# cdf-single-driver.net
KiCad netlist of a schematic drawn in EAGLE
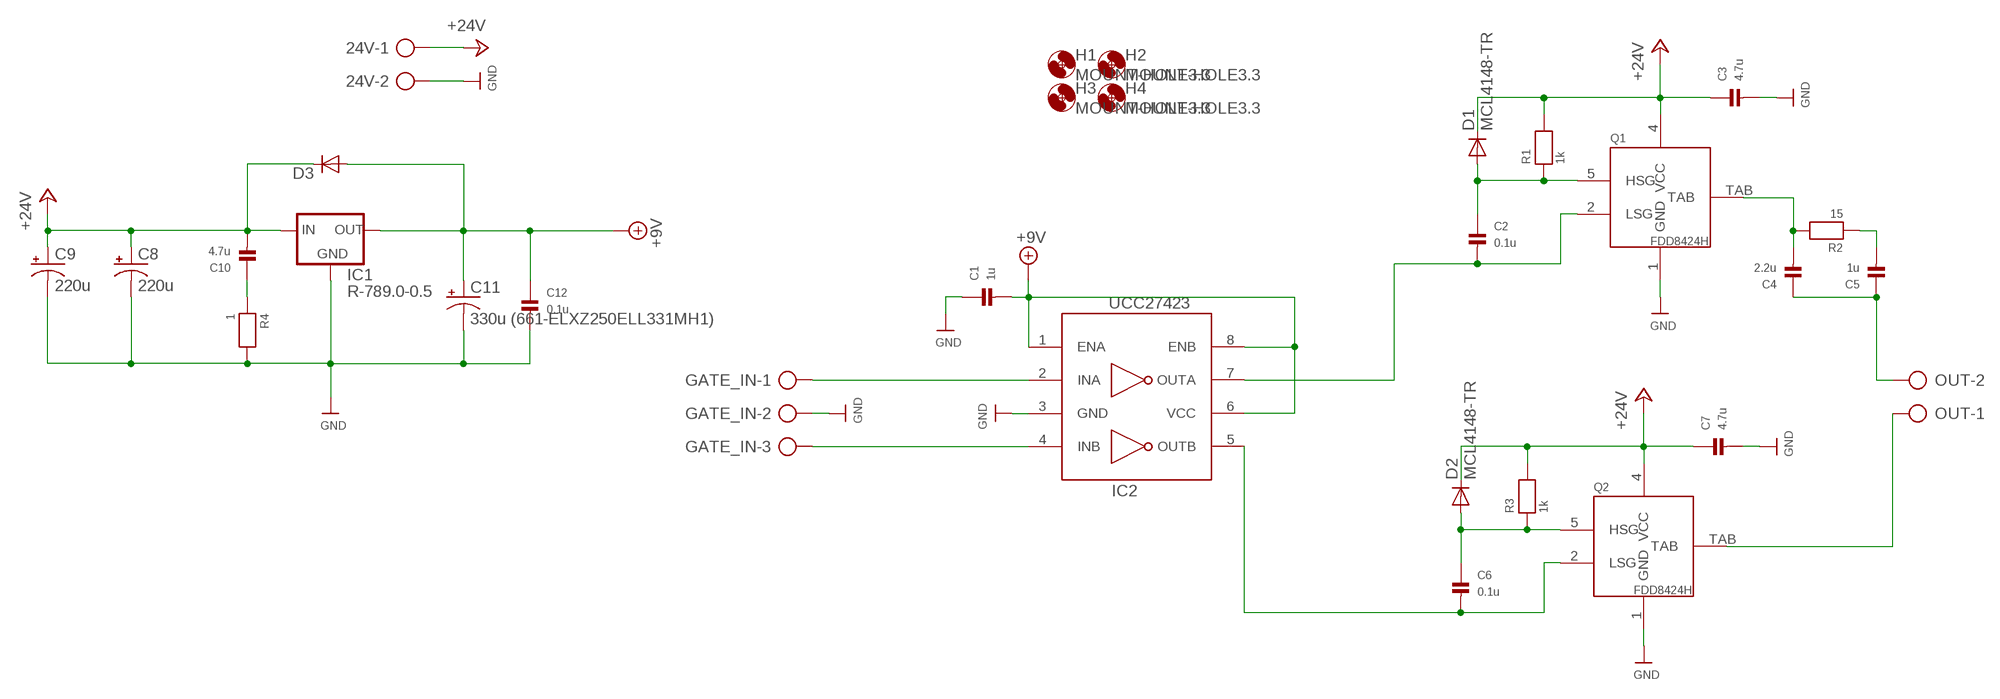
[diagram p0: schematic, sheet 1]

(export (version "E")
  (design (tool "Eeschema 10.0.6"))
  (components
    (comp (ref "24V")
      (value "AK500/2")
      (footprint "eagle-import:AK500_2")
      (libsource (lib "eagle-import") (part "AK500/2"))
    )
    (comp (ref "C1")
      (value "1u")
      (footprint "eagle-import:0805")
      (libsource (lib "eagle-import") (part "CAP_CERAMIC0805"))
    )
    (comp (ref "C2")
      (value "0.1u")
      (footprint "eagle-import:0805")
      (libsource (lib "eagle-import") (part "CAP_CERAMIC0805"))
    )
    (comp (ref "C3")
      (value "4.7u")
      (footprint "eagle-import:0805")
      (libsource (lib "eagle-import") (part "CAP_CERAMIC0805"))
    )
    (comp (ref "C4")
      (value "2.2u")
      (footprint "eagle-import:0805")
      (libsource (lib "eagle-import") (part "CAP_CERAMIC0805"))
    )
    (comp (ref "C5")
      (value "1u")
      (footprint "eagle-import:0805")
      (libsource (lib "eagle-import") (part "CAP_CERAMIC0805"))
    )
    (comp (ref "C6")
      (value "0.1u")
      (footprint "eagle-import:0805")
      (libsource (lib "eagle-import") (part "CAP_CERAMIC0805"))
    )
    (comp (ref "C7")
      (value "4.7u")
      (footprint "eagle-import:0805")
      (libsource (lib "eagle-import") (part "CAP_CERAMIC0805"))
    )
    (comp (ref "C8")
      (value "220u")
      (footprint "eagle-import:E3,5-8")
      (libsource (lib "eagle-import") (part "CPOL-USE3.5-8"))
    )
    (comp (ref "C9")
      (value "220u")
      (footprint "eagle-import:E3,5-8")
      (libsource (lib "eagle-import") (part "CPOL-USE3.5-8"))
    )
    (comp (ref "C10")
      (value "4.7u")
      (footprint "eagle-import:0805")
      (libsource (lib "eagle-import") (part "CAP_CERAMIC0805"))
    )
    (comp (ref "C11")
      (value "330u (661-ELXZ250ELL331MH1)")
      (footprint "eagle-import:E3,5-8")
      (libsource (lib "eagle-import") (part "CPOL-USE3.5-8"))
    )
    (comp (ref "C12")
      (value "0.1u")
      (footprint "eagle-import:0805")
      (libsource (lib "eagle-import") (part "CAP_CERAMIC0805"))
    )
    (comp (ref "D1")
      (value "MCL4148-TR")
      (footprint "eagle-import:MICROMELF-W")
      (libsource (lib "eagle-import") (part "DIODE-MICROMELF-W"))
    )
    (comp (ref "D2")
      (value "MCL4148-TR")
      (footprint "eagle-import:MICROMELF-W")
      (libsource (lib "eagle-import") (part "DIODE-MICROMELF-W"))
    )
    (comp (ref "D3")
      (value "DIODE-SOD123")
      (footprint "eagle-import:SOD123")
      (libsource (lib "eagle-import") (part "DIODE-SOD123"))
    )
    (comp (ref "GATE_IN")
      (value "AK500/3")
      (footprint "eagle-import:AK500_3")
      (libsource (lib "eagle-import") (part "AK500/3"))
    )
    (comp (ref "H1")
      (value "MOUNT-HOLE3.3")
      (footprint "eagle-import:3,3")
      (libsource (lib "eagle-import") (part "MOUNT-HOLE3.3"))
    )
    (comp (ref "H2")
      (value "MOUNT-HOLE3.3")
      (footprint "eagle-import:3,3")
      (libsource (lib "eagle-import") (part "MOUNT-HOLE3.3"))
    )
    (comp (ref "H3")
      (value "MOUNT-HOLE3.3")
      (footprint "eagle-import:3,3")
      (libsource (lib "eagle-import") (part "MOUNT-HOLE3.3"))
    )
    (comp (ref "H4")
      (value "MOUNT-HOLE3.3")
      (footprint "eagle-import:3,3")
      (libsource (lib "eagle-import") (part "MOUNT-HOLE3.3"))
    )
    (comp (ref "IC1")
      (value "R-789.0-0.5")
      (footprint "eagle-import:SIP3")
      (fields (field (name "MF") "Recom") (field (name "MPN") "R-789.0-05"))
      (libsource (lib "eagle-import") (part "R-78-0.59.0"))
    )
    (comp (ref "IC2")
      (value "UCC27423")
      (footprint "eagle-import:SOIC8")
      (libsource (lib "eagle-import") (part "UCC27423"))
    )
    (comp (ref "OUT")
      (value "AK500/2")
      (footprint "eagle-import:AK500_2")
      (libsource (lib "eagle-import") (part "AK500/2"))
    )
    (comp (ref "Q1")
      (value "FDD8424H")
      (footprint "eagle-import:TO252-4")
      (libsource (lib "eagle-import") (part "FDD8424H"))
    )
    (comp (ref "Q2")
      (value "FDD8424H")
      (footprint "eagle-import:TO252-4")
      (libsource (lib "eagle-import") (part "FDD8424H"))
    )
    (comp (ref "R1")
      (value "1k")
      (footprint "eagle-import:0805")
      (libsource (lib "eagle-import") (part "RESISTOR0805"))
    )
    (comp (ref "R2")
      (value "15")
      (footprint "eagle-import:0805")
      (libsource (lib "eagle-import") (part "RESISTOR0805"))
    )
    (comp (ref "R3")
      (value "1k")
      (footprint "eagle-import:0805")
      (libsource (lib "eagle-import") (part "RESISTOR0805"))
    )
    (comp (ref "R4")
      (value "1")
      (footprint "eagle-import:0805")
      (libsource (lib "eagle-import") (part "RESISTOR0805"))
    )
  )
  (nets
    (net (code "1") (name "+9V") (class "Default")
      (node (ref "C1") (pin "2") (pinfunction "P$2_2") (pintype "passive"))
      (node (ref "C11") (pin "+") (pinfunction "+_+") (pintype "passive"))
      (node (ref "C12") (pin "1") (pinfunction "P$1_1") (pintype "passive"))
      (node (ref "D3") (pin "A") (pinfunction "A_A") (pintype "passive"))
      (node (ref "IC1") (pin "3") (pinfunction "OUT_3") (pintype "passive"))
      (node (ref "IC2") (pin "1") (pinfunction "ENA_1") (pintype "bidirectional"))
      (node (ref "IC2") (pin "6") (pinfunction "VCC_6") (pintype "bidirectional"))
      (node (ref "IC2") (pin "8") (pinfunction "ENB_8") (pintype "bidirectional"))
    )
    (net (code "2") (name "+24V") (class "Default")
      (node (ref "24V") (pin "1") (pinfunction "KL_1") (pintype "passive"))
      (node (ref "C10") (pin "2") (pinfunction "P$2_2") (pintype "passive"))
      (node (ref "C3") (pin "1") (pinfunction "P$1_1") (pintype "passive"))
      (node (ref "C7") (pin "1") (pinfunction "P$1_1") (pintype "passive"))
      (node (ref "C8") (pin "+") (pinfunction "+_+") (pintype "passive"))
      (node (ref "C9") (pin "+") (pinfunction "+_+") (pintype "passive"))
      (node (ref "D1") (pin "C") (pinfunction "C_C") (pintype "passive"))
      (node (ref "D2") (pin "C") (pinfunction "C_C") (pintype "passive"))
      (node (ref "D3") (pin "C") (pinfunction "C_C") (pintype "passive"))
      (node (ref "IC1") (pin "1") (pinfunction "IN_1") (pintype "input"))
      (node (ref "Q1") (pin "4") (pinfunction "VCC_4") (pintype "bidirectional"))
      (node (ref "Q2") (pin "4") (pinfunction "VCC_4") (pintype "bidirectional"))
      (node (ref "R1") (pin "2") (pinfunction "2_2") (pintype "passive"))
      (node (ref "R3") (pin "2") (pinfunction "2_2") (pintype "passive"))
    )
    (net (code "3") (name "GND") (class "Default")
      (node (ref "24V") (pin "2") (pinfunction "KL_2") (pintype "passive"))
      (node (ref "C1") (pin "1") (pinfunction "P$1_1") (pintype "passive"))
      (node (ref "C11") (pin "-") (pinfunction "-_-") (pintype "passive"))
      (node (ref "C12") (pin "2") (pinfunction "P$2_2") (pintype "passive"))
      (node (ref "C3") (pin "2") (pinfunction "P$2_2") (pintype "passive"))
      (node (ref "C7") (pin "2") (pinfunction "P$2_2") (pintype "passive"))
      (node (ref "C8") (pin "-") (pinfunction "-_-") (pintype "passive"))
      (node (ref "C9") (pin "-") (pinfunction "-_-") (pintype "passive"))
      (node (ref "GATE_IN") (pin "2") (pinfunction "KL_2") (pintype "passive"))
      (node (ref "IC1") (pin "2") (pinfunction "GND_2") (pintype "input"))
      (node (ref "IC2") (pin "3") (pinfunction "GND_3") (pintype "bidirectional"))
      (node (ref "Q1") (pin "1") (pinfunction "GND_1") (pintype "bidirectional"))
      (node (ref "Q2") (pin "1") (pinfunction "GND_1") (pintype "bidirectional"))
      (node (ref "R4") (pin "2") (pinfunction "2_2") (pintype "passive"))
    )
    (net (code "4") (name "Net-(C2-P$1)") (class "Default")
      (node (ref "C2") (pin "1") (pinfunction "P$1_1") (pintype "passive"))
      (node (ref "D1") (pin "A") (pinfunction "A_A") (pintype "passive"))
      (node (ref "Q1") (pin "5") (pinfunction "HSG_5") (pintype "bidirectional"))
      (node (ref "R1") (pin "1") (pinfunction "1_1") (pintype "passive"))
    )
    (net (code "5") (name "Net-(C2-P$2)") (class "Default")
      (node (ref "C2") (pin "2") (pinfunction "P$2_2") (pintype "passive"))
      (node (ref "IC2") (pin "7") (pinfunction "OUTA_7") (pintype "bidirectional"))
      (node (ref "Q1") (pin "2") (pinfunction "LSG_2") (pintype "bidirectional"))
    )
    (net (code "6") (name "Net-(C4-P$1)") (class "Default")
      (node (ref "C4") (pin "1") (pinfunction "P$1_1") (pintype "passive"))
      (node (ref "C5") (pin "1") (pinfunction "P$1_1") (pintype "passive"))
      (node (ref "OUT") (pin "2") (pinfunction "KL_2") (pintype "passive"))
    )
    (net (code "7") (name "Net-(C4-P$2)") (class "Default")
      (node (ref "C4") (pin "2") (pinfunction "P$2_2") (pintype "passive"))
      (node (ref "Q1") (pin "TAB") (pinfunction "TAB_TAB") (pintype "bidirectional"))
      (node (ref "R2") (pin "2") (pinfunction "2_2") (pintype "passive"))
    )
    (net (code "8") (name "Net-(C5-P$2)") (class "Default")
      (node (ref "C5") (pin "2") (pinfunction "P$2_2") (pintype "passive"))
      (node (ref "R2") (pin "1") (pinfunction "1_1") (pintype "passive"))
    )
    (net (code "9") (name "Net-(C6-P$1)") (class "Default")
      (node (ref "C6") (pin "1") (pinfunction "P$1_1") (pintype "passive"))
      (node (ref "D2") (pin "A") (pinfunction "A_A") (pintype "passive"))
      (node (ref "Q2") (pin "5") (pinfunction "HSG_5") (pintype "bidirectional"))
      (node (ref "R3") (pin "1") (pinfunction "1_1") (pintype "passive"))
    )
    (net (code "10") (name "Net-(C6-P$2)") (class "Default")
      (node (ref "C6") (pin "2") (pinfunction "P$2_2") (pintype "passive"))
      (node (ref "IC2") (pin "5") (pinfunction "OUTB_5") (pintype "bidirectional"))
      (node (ref "Q2") (pin "2") (pinfunction "LSG_2") (pintype "bidirectional"))
    )
    (net (code "11") (name "Net-(C10-P$1)") (class "Default")
      (node (ref "C10") (pin "1") (pinfunction "P$1_1") (pintype "passive"))
      (node (ref "R4") (pin "1") (pinfunction "1_1") (pintype "passive"))
    )
    (net (code "12") (name "Net-(GATE_INA-KL)") (class "Default")
      (node (ref "GATE_IN") (pin "1") (pinfunction "KL_1") (pintype "passive"))
      (node (ref "IC2") (pin "2") (pinfunction "INA_2") (pintype "bidirectional"))
    )
    (net (code "13") (name "Net-(GATE_INC-KL)") (class "Default")
      (node (ref "GATE_IN") (pin "3") (pinfunction "KL_3") (pintype "passive"))
      (node (ref "IC2") (pin "4") (pinfunction "INB_4") (pintype "bidirectional"))
    )
    (net (code "14") (name "Net-(OUTA-KL)") (class "Default")
      (node (ref "OUT") (pin "1") (pinfunction "KL_1") (pintype "passive"))
      (node (ref "Q2") (pin "TAB") (pinfunction "TAB_TAB") (pintype "bidirectional"))
    )
  )
)
